# UKU207xx_power_board_1.net
KiCad netlist of a schematic drawn in Altium Designer
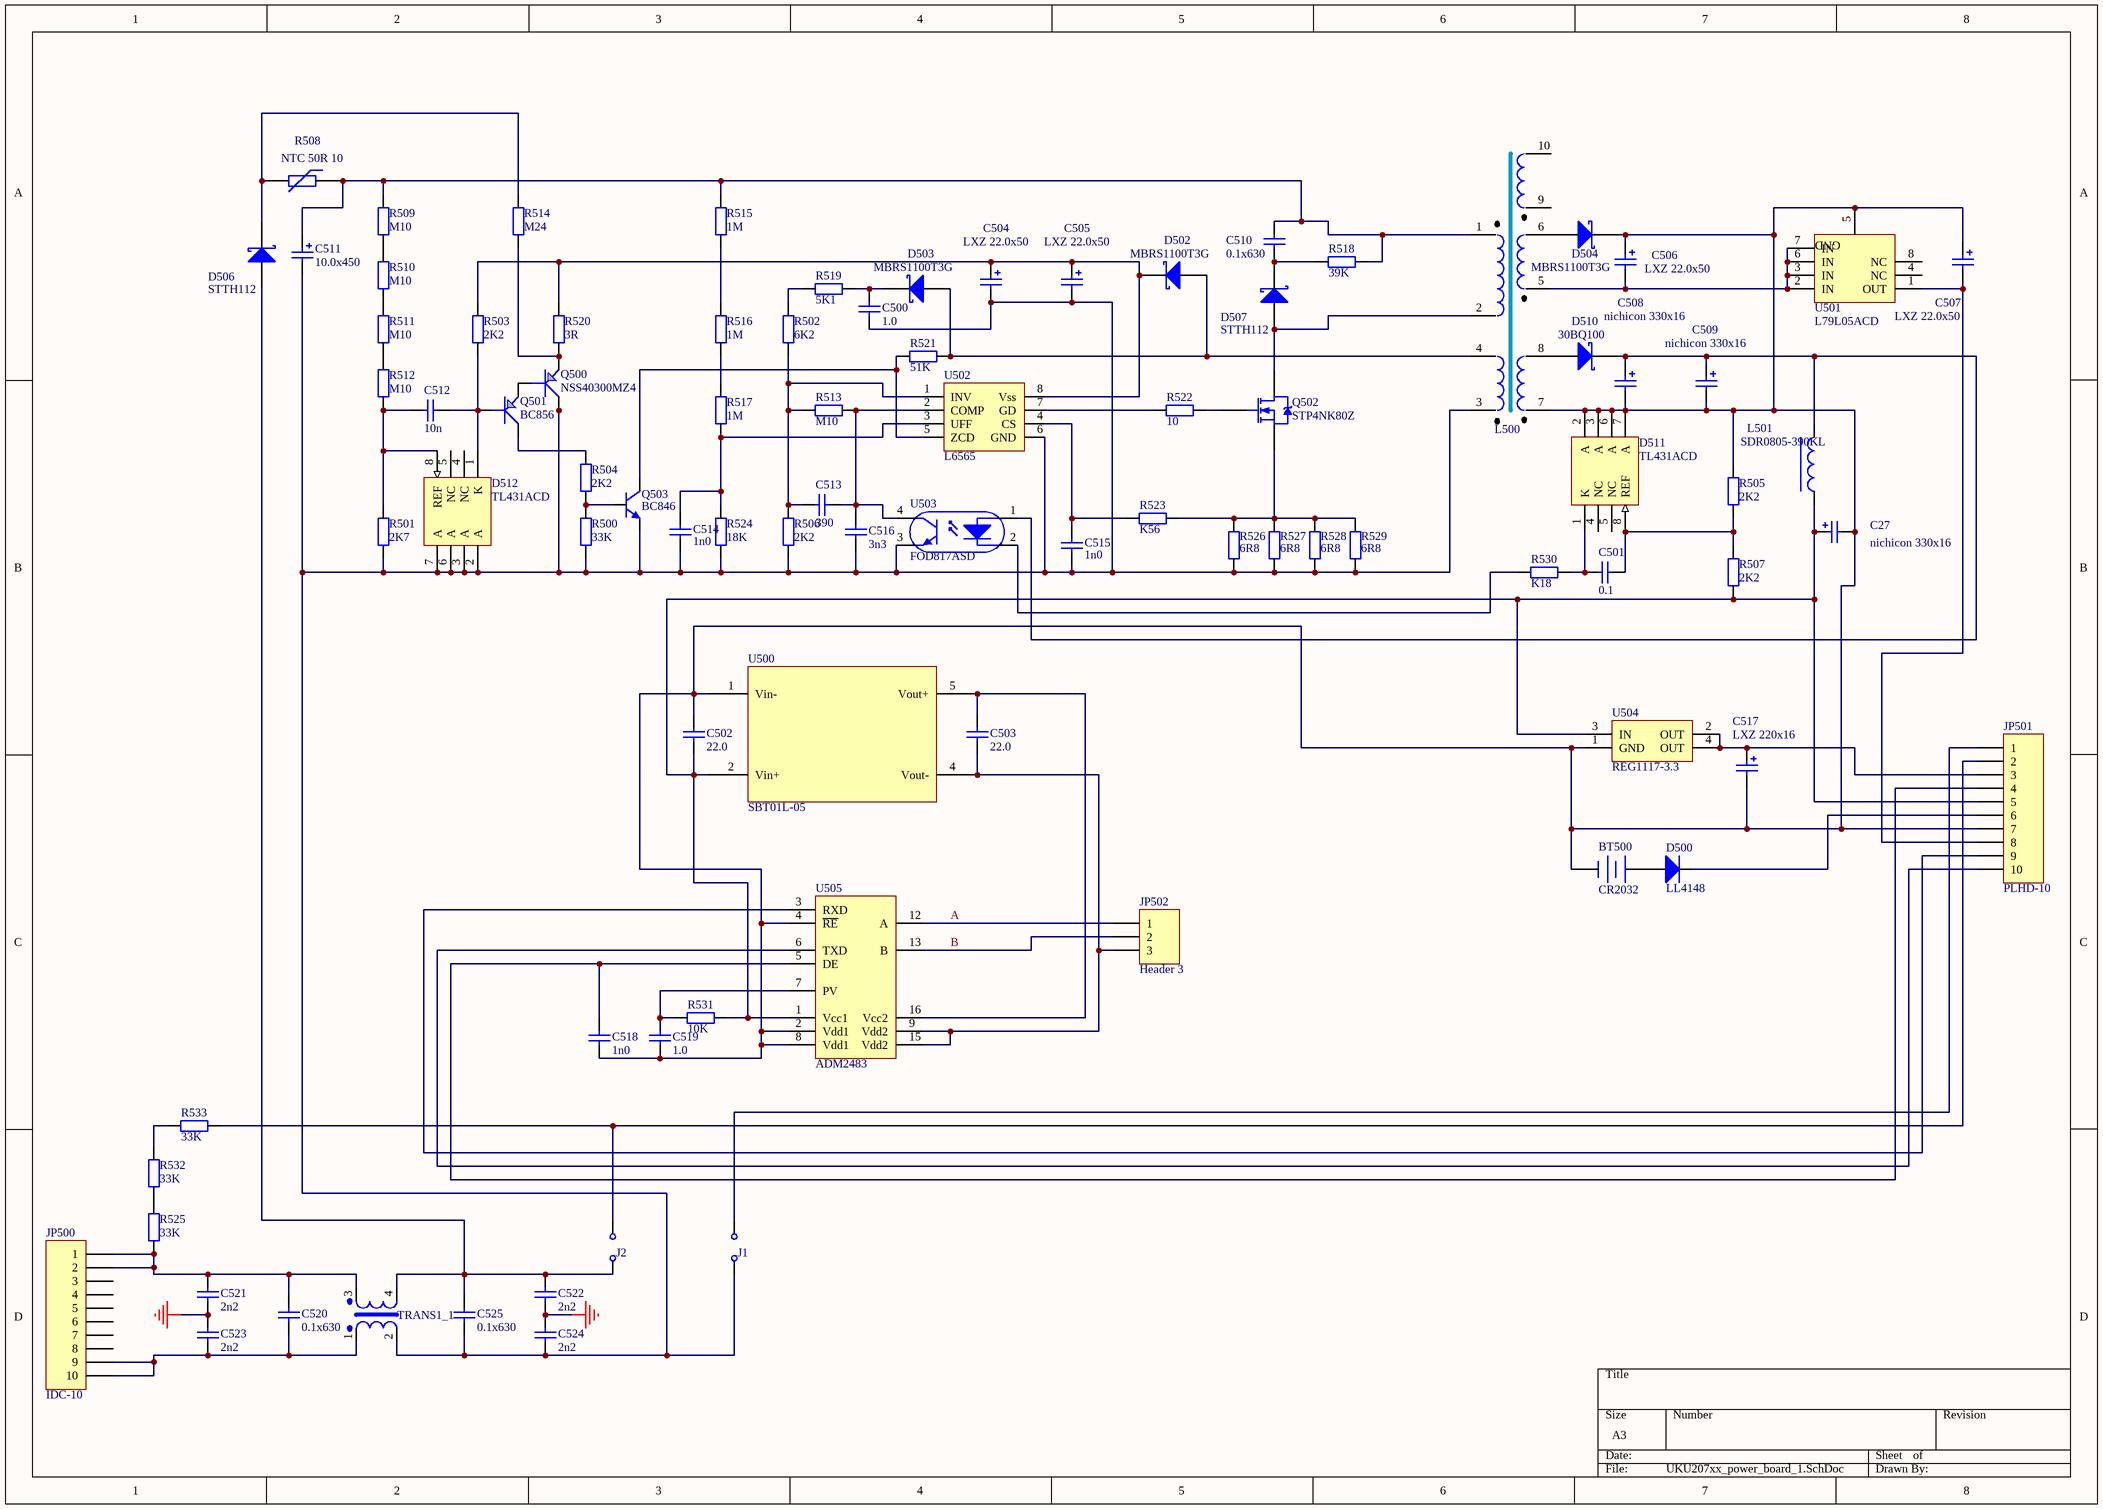
[diagram p0: UKU207xx_power_board_1.SchDoc]

(export (version "E")
  (design (tool "Eeschema 10.0.6"))
  (components
    (comp (ref "BT500")
      (value "CR2032")
      (footprint "BAT_SUPP")
      (description "Multicell Battery")
      (fields (field (name "MANUFACTURER") "Generic Components") (field (name "PUBLISHER") "Altium Limited"))
      (libsource (lib "Miscellaneous Devices") (part "Battery"))
    )
    (comp (ref "C27")
      (value "nichicon 330x16")
      (footprint "el3")
      (description "Polarized Capacitor (Radial)")
      (fields (field (name "MANUFACTURER") "Generic Components") (field (name "PUBLISHER") "Altium Limited"))
      (libsource (lib "PAL") (part "Cap Pol1"))
    )
    (comp (ref "C500")
      (value "1.0")
      (footprint "_1206")
      (description "Capacitor (Semiconductor SIM Model)")
      (fields (field (name "MANUFACTURER") "Generic Components") (field (name "PUBLISHER") "Altium Limited"))
      (libsource (lib "Miscellaneous Devices") (part "Cap Semi"))
    )
    (comp (ref "C501")
      (value "0.1")
      (footprint "_1206")
      (description "Capacitor (Semiconductor SIM Model)")
      (fields (field (name "MANUFACTURER") "Generic Components") (field (name "PUBLISHER") "Altium Limited"))
      (libsource (lib "Miscellaneous Devices") (part "Cap Semi"))
    )
    (comp (ref "C502")
      (value "22.0")
      (footprint "_1206")
      (description "Capacitor (Semiconductor SIM Model)")
      (fields (field (name "MANUFACTURER") "Generic Components") (field (name "PUBLISHER") "Altium Limited"))
      (libsource (lib "Miscellaneous Devices") (part "Cap Semi"))
    )
    (comp (ref "C503")
      (value "22.0")
      (footprint "_1206")
      (description "Capacitor (Semiconductor SIM Model)")
      (fields (field (name "MANUFACTURER") "Generic Components") (field (name "PUBLISHER") "Altium Limited"))
      (libsource (lib "Miscellaneous Devices") (part "Cap Semi"))
    )
    (comp (ref "C504")
      (value "LXZ 22.0x50")
      (footprint "el3")
      (description "Polarized Capacitor (Radial)")
      (fields (field (name "MANUFACTURER") "Generic Components") (field (name "PUBLISHER") "Altium Limited"))
      (libsource (lib "PAL") (part "Cap Pol1"))
    )
    (comp (ref "C505")
      (value "LXZ 22.0x50")
      (footprint "el3")
      (description "Polarized Capacitor (Radial)")
      (fields (field (name "MANUFACTURER") "Generic Components") (field (name "PUBLISHER") "Altium Limited"))
      (libsource (lib "PAL") (part "Cap Pol1"))
    )
    (comp (ref "C506")
      (value "LXZ 22.0x50")
      (footprint "el3")
      (description "Polarized Capacitor (Radial)")
      (fields (field (name "MANUFACTURER") "Generic Components") (field (name "PUBLISHER") "Altium Limited"))
      (libsource (lib "PAL") (part "Cap Pol1"))
    )
    (comp (ref "C507")
      (value "LXZ 22.0x50")
      (footprint "el3")
      (description "Polarized Capacitor (Radial)")
      (fields (field (name "MANUFACTURER") "Generic Components") (field (name "PUBLISHER") "Altium Limited"))
      (libsource (lib "PAL") (part "Cap Pol1"))
    )
    (comp (ref "C508")
      (value "nichicon 330x16")
      (footprint "el3")
      (description "Polarized Capacitor (Radial)")
      (fields (field (name "MANUFACTURER") "Generic Components") (field (name "PUBLISHER") "Altium Limited"))
      (libsource (lib "PAL") (part "Cap Pol1"))
    )
    (comp (ref "C509")
      (value "nichicon 330x16")
      (footprint "el3")
      (description "Polarized Capacitor (Radial)")
      (fields (field (name "MANUFACTURER") "Generic Components") (field (name "PUBLISHER") "Altium Limited"))
      (libsource (lib "PAL") (part "Cap Pol1"))
    )
    (comp (ref "C510")
      (value "0.1x630")
      (footprint "c15")
      (description "Capacitor (Semiconductor SIM Model)")
      (fields (field (name "MANUFACTURER") "Generic Components") (field (name "PUBLISHER") "Altium Limited"))
      (libsource (lib "Miscellaneous Devices") (part "Cap Semi"))
    )
    (comp (ref "C511")
      (value "10.0x450")
      (footprint "el_15_25_h")
      (description "Polarized Capacitor (Radial)")
      (fields (field (name "MANUFACTURER") "Generic Components") (field (name "PUBLISHER") "Altium Limited"))
      (libsource (lib "PAL") (part "Cap Pol1"))
    )
    (comp (ref "C512")
      (value "10n")
      (footprint "_1206")
      (description "Capacitor (Semiconductor SIM Model)")
      (fields (field (name "MANUFACTURER") "Generic Components") (field (name "PUBLISHER") "Altium Limited"))
      (libsource (lib "Miscellaneous Devices") (part "Cap Semi"))
    )
    (comp (ref "C513")
      (value "390")
      (footprint "_1206")
      (description "Capacitor (Semiconductor SIM Model)")
      (fields (field (name "MANUFACTURER") "Generic Components") (field (name "PUBLISHER") "Altium Limited"))
      (libsource (lib "Miscellaneous Devices") (part "Cap Semi"))
    )
    (comp (ref "C514")
      (value "1n0")
      (footprint "_1206")
      (description "Capacitor (Semiconductor SIM Model)")
      (fields (field (name "MANUFACTURER") "Generic Components") (field (name "PUBLISHER") "Altium Limited"))
      (libsource (lib "Miscellaneous Devices") (part "Cap Semi"))
    )
    (comp (ref "C515")
      (value "1n0")
      (footprint "_1206")
      (description "Capacitor (Semiconductor SIM Model)")
      (fields (field (name "MANUFACTURER") "Generic Components") (field (name "PUBLISHER") "Altium Limited"))
      (libsource (lib "Miscellaneous Devices") (part "Cap Semi"))
    )
    (comp (ref "C516")
      (value "3n3")
      (footprint "_1206")
      (description "Capacitor (Semiconductor SIM Model)")
      (fields (field (name "MANUFACTURER") "Generic Components") (field (name "PUBLISHER") "Altium Limited"))
      (libsource (lib "Miscellaneous Devices") (part "Cap Semi"))
    )
    (comp (ref "C517")
      (value "LXZ 220x16")
      (footprint "el3")
      (description "Polarized Capacitor (Radial)")
      (fields (field (name "MANUFACTURER") "Generic Components") (field (name "PUBLISHER") "Altium Limited"))
      (libsource (lib "PAL") (part "Cap Pol1"))
    )
    (comp (ref "C518")
      (value "1n0")
      (footprint "_1206")
      (description "Capacitor (Semiconductor SIM Model)")
      (fields (field (name "MANUFACTURER") "Generic Components") (field (name "PUBLISHER") "Altium Limited"))
      (libsource (lib "Miscellaneous Devices") (part "Cap Semi"))
    )
    (comp (ref "C519")
      (value "1.0")
      (footprint "_1206")
      (description "Capacitor (Semiconductor SIM Model)")
      (fields (field (name "MANUFACTURER") "Generic Components") (field (name "PUBLISHER") "Altium Limited"))
      (libsource (lib "Miscellaneous Devices") (part "Cap Semi"))
    )
    (comp (ref "C520")
      (value "0.1x630")
      (footprint "c15")
      (description "Capacitor (Semiconductor SIM Model)")
      (fields (field (name "MANUFACTURER") "Generic Components") (field (name "PUBLISHER") "Altium Limited"))
      (libsource (lib "Miscellaneous Devices") (part "Cap Semi"))
    )
    (comp (ref "C521")
      (value "2n2")
      (footprint "C8")
      (description "Capacitor (Semiconductor SIM Model)")
      (fields (field (name "MANUFACTURER") "Generic Components") (field (name "PUBLISHER") "Altium Limited"))
      (libsource (lib "Miscellaneous Devices") (part "Cap Semi"))
    )
    (comp (ref "C522")
      (value "2n2")
      (footprint "c8")
      (description "Capacitor (Semiconductor SIM Model)")
      (fields (field (name "MANUFACTURER") "Generic Components") (field (name "PUBLISHER") "Altium Limited"))
      (libsource (lib "Miscellaneous Devices") (part "Cap Semi"))
    )
    (comp (ref "C523")
      (value "2n2")
      (footprint "c8")
      (description "Capacitor (Semiconductor SIM Model)")
      (fields (field (name "MANUFACTURER") "Generic Components") (field (name "PUBLISHER") "Altium Limited"))
      (libsource (lib "Miscellaneous Devices") (part "Cap Semi"))
    )
    (comp (ref "C524")
      (value "2n2")
      (footprint "c8")
      (description "Capacitor (Semiconductor SIM Model)")
      (fields (field (name "MANUFACTURER") "Generic Components") (field (name "PUBLISHER") "Altium Limited"))
      (libsource (lib "Miscellaneous Devices") (part "Cap Semi"))
    )
    (comp (ref "C525")
      (value "0.1х630")
      (footprint "c15")
      (description "Capacitor (Semiconductor SIM Model)")
      (fields (field (name "MANUFACTURER") "Generic Components") (field (name "PUBLISHER") "Altium Limited"))
      (libsource (lib "Miscellaneous Devices") (part "Cap Semi"))
    )
    (comp (ref "D500")
      (value "LL4148")
      (footprint "_1206d")
      (description "Default Diode")
      (fields (field (name "MANUFACTURER") "Generic Components") (field (name "PUBLISHER") "Altium Limited"))
      (libsource (lib "PAL") (part "Diode"))
    )
    (comp (ref "D502")
      (value "MBRS1100T3G")
      (footprint "D_6_3")
      (description "Schottky Rectifier")
      (fields
        (field (name "MANUFACTURER") "International Rectifier")
        (field (name "PUBLISHER") "Altium Limited")
      )
      (libsource (lib "IR Discrete Diode") (part "10BQ015"))
    )
    (comp (ref "D503")
      (value "MBRS1100T3G")
      (footprint "D_6_3")
      (description "Schottky Rectifier")
      (fields
        (field (name "MANUFACTURER") "International Rectifier")
        (field (name "PUBLISHER") "Altium Limited")
      )
      (libsource (lib "IR Discrete Diode") (part "10BQ015"))
    )
    (comp (ref "D504")
      (value "MBRS1100T3G")
      (footprint "D_6_3")
      (description "Schottky Rectifier")
      (fields
        (field (name "MANUFACTURER") "International Rectifier")
        (field (name "PUBLISHER") "Altium Limited")
      )
      (libsource (lib "IR Discrete Diode") (part "10BQ015"))
    )
    (comp (ref "D506")
      (value "STTH112")
      (footprint "D_6_3")
      (description "Schottky Diode")
      (fields
        (field (name "MANUFACTURER") "International Rectifier")
        (field (name "PUBLISHER") "Altium Limited")
      )
      (libsource (lib "IR Discrete Diode") (part "10BQ015"))
    )
    (comp (ref "D507")
      (value "STTH112")
      (footprint "D_6_3")
      (description "Schottky Diode")
      (fields
        (field (name "MANUFACTURER") "International Rectifier")
        (field (name "PUBLISHER") "Altium Limited")
      )
      (libsource (lib "IR Discrete Diode") (part "10BQ015"))
    )
    (comp (ref "D510")
      (value "30BQ100")
      (footprint "30BQ100")
      (description "Schottky Rectifier")
      (fields
        (field (name "MANUFACTURER") "International Rectifier")
        (field (name "PUBLISHER") "Altium Limited")
      )
      (libsource (lib "IR Discrete Diode") (part "10BQ015"))
    )
    (comp (ref "D511")
      (value "TL431ACD")
      (footprint "SO-G8")
      (description "Programmable Precision Reference")
      (fields (field (name "MANUFACTURER") "Motorola") (field (name "PUBLISHER") "Altium Limited"))
      (libsource (lib "") (part "TL431ACD_1"))
    )
    (comp (ref "D512")
      (value "TL431ACD")
      (footprint "SO-G8")
      (description "Programmable Precision Reference")
      (fields (field (name "MANUFACTURER") "Motorola") (field (name "PUBLISHER") "Altium Limited"))
      (libsource (lib "Motorola Power Management Voltage Reference") (part "TL431ACD"))
    )
    (comp (ref "J1")
      (value "~")
      (footprint "BT5-2")
      (description "Switch")
      (fields (field (name "MANUFACTURER") "Generic Components") (field (name "PUBLISHER") "Altium Limited"))
      (libsource (lib "PAL") (part "JMP"))
    )
    (comp (ref "J2")
      (value "~")
      (footprint "BT5-2")
      (description "Switch")
      (fields (field (name "MANUFACTURER") "Generic Components") (field (name "PUBLISHER") "Altium Limited"))
      (libsource (lib "PAL") (part "JMP"))
    )
    (comp (ref "JP500")
      (value "IDC-10")
      (footprint "HDR2X5")
      (description "Header, 10-Pin")
      (fields (field (name "MANUFACTURER") "Generic Components") (field (name "PUBLISHER") "Altium Limited"))
      (libsource (lib "Miscellaneous Connectors") (part "Header 10"))
    )
    (comp (ref "JP501")
      (value "PLHD-10")
      (footprint "HDR2X5")
      (description "Header, 10-Pin")
      (fields (field (name "MANUFACTURER") "Generic Components") (field (name "PUBLISHER") "Altium Limited"))
      (libsource (lib "") (part "Header 10_1"))
    )
    (comp (ref "JP502")
      (value "Header 3")
      (footprint "2EDG-5.08-3P")
      (description "Header, 3-Pin")
      (fields (field (name "MANUFACTURER") "Generic Components") (field (name "PUBLISHER") "Altium Limited"))
      (libsource (lib "Miscellaneous Connectors") (part "Header 3"))
    )
    (comp (ref "L500")
      (value "L220-K10")
      (footprint "trans_ring1")
      (description "Дроссель")
      (libsource (lib "PAL") (part "L1_dc_2"))
    )
    (comp (ref "L501")
      (value "SDR0805-390KL")
      (footprint "L10x10")
      (description "Magnetic-Core Inductor")
      (fields (field (name "MANUFACTURER") "Generic Components") (field (name "PUBLISHER") "Altium Limited"))
      (libsource (lib "PAL") (part "Inductor Konstr 2"))
    )
    (comp (ref "Q500")
      (value "NSS40300MZ4")
      (footprint "DSO-G3")
      (libsource (lib "PAL") (part "NSS40300MZ4"))
    )
    (comp (ref "Q501")
      (value "BC856")
      (footprint "SO-G3")
      (description "Bipolar transistor")
      (libsource (lib "MAIN") (part "GT109"))
    )
    (comp (ref "Q502")
      (value "STP4NK80Z")
      (footprint "TO220_h")
      (description "N-Channel Power MOSFET")
      (fields (field (name "MANUFACTURER") "Generic Components") (field (name "PUBLISHER") "Altium Limited"))
      (libsource (lib "Miscellaneous Devices") (part "NMOS-2"))
    )
    (comp (ref "Q503")
      (value "BC846")
      (footprint "SO-G3")
      (description "General Purpose Transistor NPN Silicon")
      (fields (field (name "MANUFACTURER") "Motorola") (field (name "PUBLISHER") "Altium Limited"))
      (libsource (lib "PAL") (part "BC847ALT1"))
    )
    (comp (ref "R500")
      (value "33K")
      (footprint "_1206")
      (description "Resistor")
      (fields (field (name "MANUFACTURER") "Generic Components") (field (name "PUBLISHER") "Altium Limited"))
      (libsource (lib "") (part "Res2_2"))
    )
    (comp (ref "R501")
      (value "2K7")
      (footprint "_1206")
      (description "Resistor")
      (fields (field (name "MANUFACTURER") "Generic Components") (field (name "PUBLISHER") "Altium Limited"))
      (libsource (lib "") (part "Res2_2"))
    )
    (comp (ref "R502")
      (value "6K2")
      (footprint "_1206")
      (description "Resistor")
      (fields (field (name "MANUFACTURER") "Generic Components") (field (name "PUBLISHER") "Altium Limited"))
      (libsource (lib "") (part "Res2_2"))
    )
    (comp (ref "R503")
      (value "2K2")
      (footprint "_1206")
      (description "Resistor")
      (fields (field (name "MANUFACTURER") "Generic Components") (field (name "PUBLISHER") "Altium Limited"))
      (libsource (lib "") (part "Res2_2"))
    )
    (comp (ref "R504")
      (value "2K2")
      (footprint "_1206")
      (description "Resistor")
      (fields (field (name "MANUFACTURER") "Generic Components") (field (name "PUBLISHER") "Altium Limited"))
      (libsource (lib "") (part "Res2_2"))
    )
    (comp (ref "R505")
      (value "2K2")
      (footprint "_1206")
      (description "Resistor")
      (fields (field (name "MANUFACTURER") "Generic Components") (field (name "PUBLISHER") "Altium Limited"))
      (libsource (lib "") (part "Res2_2"))
    )
    (comp (ref "R506")
      (value "2K2")
      (footprint "_1206")
      (description "Resistor")
      (fields (field (name "MANUFACTURER") "Generic Components") (field (name "PUBLISHER") "Altium Limited"))
      (libsource (lib "") (part "Res2_2"))
    )
    (comp (ref "R507")
      (value "2K2")
      (footprint "_1206")
      (description "Resistor")
      (fields (field (name "MANUFACTURER") "Generic Components") (field (name "PUBLISHER") "Altium Limited"))
      (libsource (lib "") (part "Res2_2"))
    )
    (comp (ref "R508")
      (value "NTC 50R 10")
      (footprint "JVR07N")
      (description "Varistor (Voltage-Sensitive Resistor)")
      (fields (field (name "MANUFACTURER") "Generic Components") (field (name "PUBLISHER") "Altium Limited"))
      (libsource (lib "Miscellaneous Devices") (part "Res Varistor"))
    )
    (comp (ref "R509")
      (value "M10")
      (footprint "_1206")
      (description "Resistor")
      (fields (field (name "MANUFACTURER") "Generic Components") (field (name "PUBLISHER") "Altium Limited"))
      (libsource (lib "") (part "Res2_2"))
    )
    (comp (ref "R510")
      (value "M10")
      (footprint "_1206")
      (description "Resistor")
      (fields (field (name "MANUFACTURER") "Generic Components") (field (name "PUBLISHER") "Altium Limited"))
      (libsource (lib "") (part "Res2_2"))
    )
    (comp (ref "R511")
      (value "M10")
      (footprint "_1206")
      (description "Resistor")
      (fields (field (name "MANUFACTURER") "Generic Components") (field (name "PUBLISHER") "Altium Limited"))
      (libsource (lib "") (part "Res2_2"))
    )
    (comp (ref "R512")
      (value "M10")
      (footprint "_1206")
      (description "Resistor")
      (fields (field (name "MANUFACTURER") "Generic Components") (field (name "PUBLISHER") "Altium Limited"))
      (libsource (lib "") (part "Res2_2"))
    )
    (comp (ref "R513")
      (value "M10")
      (footprint "_1206")
      (description "Resistor")
      (fields (field (name "MANUFACTURER") "Generic Components") (field (name "PUBLISHER") "Altium Limited"))
      (libsource (lib "") (part "Res2_1"))
    )
    (comp (ref "R514")
      (value "M24")
      (footprint "AXIAL-0.7")
      (description "Resistor")
      (fields (field (name "MANUFACTURER") "Generic Components") (field (name "PUBLISHER") "Altium Limited"))
      (libsource (lib "") (part "Res2_2"))
    )
    (comp (ref "R515")
      (value "1M")
      (footprint "_1206")
      (description "Resistor")
      (fields (field (name "MANUFACTURER") "Generic Components") (field (name "PUBLISHER") "Altium Limited"))
      (libsource (lib "") (part "Res2_2"))
    )
    (comp (ref "R516")
      (value "1M")
      (footprint "_1206")
      (description "Resistor")
      (fields (field (name "MANUFACTURER") "Generic Components") (field (name "PUBLISHER") "Altium Limited"))
      (libsource (lib "") (part "Res2_2"))
    )
    (comp (ref "R517")
      (value "1M")
      (footprint "_1206")
      (description "Resistor")
      (fields (field (name "MANUFACTURER") "Generic Components") (field (name "PUBLISHER") "Altium Limited"))
      (libsource (lib "") (part "Res2_2"))
    )
    (comp (ref "R518")
      (value "39K")
      (footprint "AXIAL-0.7")
      (description "Resistor")
      (fields (field (name "MANUFACTURER") "Generic Components") (field (name "PUBLISHER") "Altium Limited"))
      (libsource (lib "") (part "Res2_1"))
    )
    (comp (ref "R519")
      (value "5K1")
      (footprint "_1206")
      (description "Resistor")
      (fields (field (name "MANUFACTURER") "Generic Components") (field (name "PUBLISHER") "Altium Limited"))
      (libsource (lib "") (part "Res2_1"))
    )
    (comp (ref "R520")
      (value "3R")
      (footprint "_1206")
      (description "Resistor")
      (fields (field (name "MANUFACTURER") "Generic Components") (field (name "PUBLISHER") "Altium Limited"))
      (libsource (lib "") (part "Res2_2"))
    )
    (comp (ref "R521")
      (value "51K")
      (footprint "_1206")
      (description "Resistor")
      (fields (field (name "MANUFACTURER") "Generic Components") (field (name "PUBLISHER") "Altium Limited"))
      (libsource (lib "") (part "Res2_1"))
    )
    (comp (ref "R522")
      (value "10")
      (footprint "_1206")
      (description "Resistor")
      (fields (field (name "MANUFACTURER") "Generic Components") (field (name "PUBLISHER") "Altium Limited"))
      (libsource (lib "") (part "Res2_1"))
    )
    (comp (ref "R523")
      (value "K56")
      (footprint "_1206")
      (description "Resistor")
      (fields (field (name "MANUFACTURER") "Generic Components") (field (name "PUBLISHER") "Altium Limited"))
      (libsource (lib "") (part "Res2_1"))
    )
    (comp (ref "R524")
      (value "18K")
      (footprint "_1206")
      (description "Resistor")
      (fields (field (name "MANUFACTURER") "Generic Components") (field (name "PUBLISHER") "Altium Limited"))
      (libsource (lib "") (part "Res2_2"))
    )
    (comp (ref "R525")
      (value "33K")
      (footprint "_1206")
      (description "Resistor")
      (fields (field (name "MANUFACTURER") "Generic Components") (field (name "PUBLISHER") "Altium Limited"))
      (libsource (lib "Miscellaneous Devices") (part "Res2"))
    )
    (comp (ref "R526")
      (value "6R8")
      (footprint "_1206")
      (description "Resistor")
      (fields (field (name "MANUFACTURER") "Generic Components") (field (name "PUBLISHER") "Altium Limited"))
      (libsource (lib "Miscellaneous Devices") (part "Res2"))
    )
    (comp (ref "R527")
      (value "6R8")
      (footprint "_1206")
      (description "Resistor")
      (fields (field (name "MANUFACTURER") "Generic Components") (field (name "PUBLISHER") "Altium Limited"))
      (libsource (lib "Miscellaneous Devices") (part "Res2"))
    )
    (comp (ref "R528")
      (value "6R8")
      (footprint "_1206")
      (description "Resistor")
      (fields (field (name "MANUFACTURER") "Generic Components") (field (name "PUBLISHER") "Altium Limited"))
      (libsource (lib "Miscellaneous Devices") (part "Res2"))
    )
    (comp (ref "R529")
      (value "6R8")
      (footprint "_1206")
      (description "Resistor")
      (fields (field (name "MANUFACTURER") "Generic Components") (field (name "PUBLISHER") "Altium Limited"))
      (libsource (lib "Miscellaneous Devices") (part "Res2"))
    )
    (comp (ref "R530")
      (value "K18")
      (footprint "_1206")
      (description "Resistor")
      (fields (field (name "MANUFACTURER") "Generic Components") (field (name "PUBLISHER") "Altium Limited"))
      (libsource (lib "") (part "Res2_1"))
    )
    (comp (ref "R531")
      (value "10K")
      (footprint "_1206")
      (description "Resistor")
      (fields (field (name "MANUFACTURER") "Generic Components") (field (name "PUBLISHER") "Altium Limited"))
      (libsource (lib "") (part "Res2_1"))
    )
    (comp (ref "R532")
      (value "33K")
      (footprint "_1206")
      (description "Resistor")
      (fields (field (name "MANUFACTURER") "Generic Components") (field (name "PUBLISHER") "Altium Limited"))
      (libsource (lib "Miscellaneous Devices") (part "Res2"))
    )
    (comp (ref "R533")
      (value "33K")
      (footprint "_1206")
      (description "Resistor")
      (fields (field (name "MANUFACTURER") "Generic Components") (field (name "PUBLISHER") "Altium Limited"))
      (libsource (lib "") (part "Res2_1"))
    )
    (comp (ref "T500")
      (value "TRANS1_1")
      (footprint "3030R4")
      (fields (field (name "MANUFACTURER") "Generic Components") (field (name "PUBLISHER") "Altium Limited"))
      (libsource (lib "PAL") (part "TRANS1_1"))
    )
    (comp (ref "U500") (value "SBT01L-05") (footprint "SBT01DET01") (libsource (lib "PAL") (part "SBT01L")))
    (comp (ref "U501")
      (value "L79L05ACD")
      (footprint "SO-G8")
      (description "Negative Voltage Regulator")
      (fields (field (name "MANUFACTURER") "ST-Microelectronics") (field (name "PUBLISHER") "Altium Limited"))
      (libsource (lib "ST Power Mgt Voltage Regulator") (part "L79L05ACD"))
    )
    (comp (ref "U502") (value "L6565") (footprint "so-g8") (libsource (lib "PAL") (part "L6565")))
    (comp (ref "U503") (value "FOD817ASD") (footprint "FOD817ASD") (libsource (lib "PAL") (part "F00817ASD")))
    (comp (ref "U504")
      (value "REG1117-3.3")
      (footprint "DSO-G3")
      (description "800mA and 1A Low Dropout Positive Regulator 2.85V, 3.3V, 5V, and Adjustable")
      (fields (field (name "MANUFACTURER") "Burr-Brown") (field (name "PUBLISHER") "Altium Limited"))
      (libsource (lib "BB Power Mgt Voltage Regulator") (part "REG1117-3.3"))
    )
    (comp (ref "U505") (value "ADM2483") (footprint "SO-G16/D10.4") (libsource (lib "PAL") (part "ADM2483")))
  )
  (nets
    (net (code "1") (name "/A") (class "Default")
      (node (ref "JP502") (pin "1") (pinfunction "1_1") (pintype "passive"))
      (node (ref "U505") (pin "12") (pinfunction "A_12") (pintype "passive"))
    )
    (net (code "2") (name "/B") (class "Default")
      (node (ref "JP502") (pin "2") (pinfunction "2_2") (pintype "passive"))
      (node (ref "U505") (pin "13") (pinfunction "B_13") (pintype "passive"))
    )
    (net (code "3") (name "GND_GND") (class "Default")
      (node (ref "C521") (pin "1") (pinfunction "1_1") (pintype "passive"))
      (node (ref "C522") (pin "1") (pinfunction "1_1") (pintype "passive"))
      (node (ref "C523") (pin "2") (pinfunction "2_2") (pintype "passive"))
      (node (ref "C524") (pin "2") (pinfunction "2_2") (pintype "passive"))
    )
    (net (code "4") (name "Net-(BT500-+)") (class "Default")
      (node (ref "BT500") (pin "1") (pinfunction "+_1") (pintype "passive"))
      (node (ref "D500") (pin "1") (pinfunction "A_1") (pintype "passive"))
    )
    (net (code "5") (name "Net-(BT500--)") (class "Default")
      (node (ref "BT500") (pin "2") (pinfunction "-_2") (pintype "passive"))
      (node (ref "C27") (pin "2") (pinfunction "2_2") (pintype "passive"))
      (node (ref "C502") (pin "1") (pinfunction "1_1") (pintype "passive"))
      (node (ref "C506") (pin "1") (pinfunction "1_1") (pintype "passive"))
      (node (ref "C507") (pin "1") (pinfunction "1_1") (pintype "passive"))
      (node (ref "C508") (pin "2") (pinfunction "2_2") (pintype "passive"))
      (node (ref "C509") (pin "2") (pinfunction "2_2") (pintype "passive"))
      (node (ref "C517") (pin "2") (pinfunction "2_2") (pintype "passive"))
      (node (ref "C518") (pin "1") (pinfunction "1_1") (pintype "passive"))
      (node (ref "C519") (pin "1") (pinfunction "1_1") (pintype "passive"))
      (node (ref "D504") (pin "2") (pinfunction "K_2") (pintype "passive"))
      (node (ref "D511") (pin "2") (pinfunction "A_2") (pintype "passive"))
      (node (ref "D511") (pin "3") (pinfunction "A_3") (pintype "passive"))
      (node (ref "D511") (pin "6") (pinfunction "A_6") (pintype "passive"))
      (node (ref "D511") (pin "7") (pinfunction "A_7") (pintype "passive"))
      (node (ref "JP501") (pin "7") (pinfunction "7_7") (pintype "passive"))
      (node (ref "L500") (pin "7") (pintype "passive"))
      (node (ref "R505") (pin "2") (pinfunction "2_2") (pintype "passive"))
      (node (ref "U500") (pin "1") (pinfunction "Vin-_1") (pintype "passive"))
      (node (ref "U501") (pin "5") (pinfunction "GND_5") (pintype "power_in"))
      (node (ref "U504") (pin "1") (pinfunction "GND_1") (pintype "power_in"))
      (node (ref "U505") (pin "2") (pinfunction "Vdd1_2") (pintype "passive"))
      (node (ref "U505") (pin "4") (pinfunction "~{RE}_4") (pintype "passive"))
      (node (ref "U505") (pin "8") (pinfunction "Vdd1_8") (pintype "passive"))
    )
    (net (code "6") (name "Net-(C506-Pad2)") (class "Default")
      (node (ref "C506") (pin "2") (pinfunction "2_2") (pintype "passive"))
      (node (ref "L500") (pin "5") (pintype "passive"))
      (node (ref "U501") (pin "2") (pinfunction "IN_2") (pintype "power_in"))
      (node (ref "U501") (pin "3") (pinfunction "IN_3") (pintype "power_in"))
      (node (ref "U501") (pin "6") (pinfunction "IN_6") (pintype "power_in"))
      (node (ref "U501") (pin "7") (pinfunction "IN_7") (pintype "power_in"))
    )
    (net (code "7") (name "Net-(C510-Pad2)") (class "Default")
      (node (ref "C510") (pin "2") (pinfunction "2_2") (pintype "passive"))
      (node (ref "C511") (pin "1") (pinfunction "1_1") (pintype "passive"))
      (node (ref "L500") (pin "1") (pintype "passive"))
      (node (ref "R508") (pin "1") (pinfunction "1_1") (pintype "passive"))
      (node (ref "R509") (pin "2") (pinfunction "2_2") (pintype "passive"))
      (node (ref "R515") (pin "2") (pinfunction "2_2") (pintype "passive"))
      (node (ref "R518") (pin "1") (pinfunction "1_1") (pintype "passive"))
    )
    (net (code "8") (name "Net-(C517-Pad1)") (class "Default")
      (node (ref "C517") (pin "1") (pinfunction "1_1") (pintype "passive"))
      (node (ref "JP501") (pin "3") (pinfunction "3_3") (pintype "passive"))
      (node (ref "U504") (pin "2") (pinfunction "OUT_2") (pintype "power_in"))
      (node (ref "U504") (pin "4") (pinfunction "OUT_4") (pintype "power_in"))
    )
    (net (code "9") (name "Net-(D500-K)") (class "Default")
      (node (ref "D500") (pin "2") (pinfunction "K_2") (pintype "passive"))
      (node (ref "JP501") (pin "6") (pinfunction "6_6") (pintype "passive"))
    )
    (net (code "10") (name "Net-(D502-A)") (class "Default")
      (node (ref "D502") (pin "1") (pinfunction "A_1") (pintype "passive"))
      (node (ref "D503") (pin "1") (pinfunction "A_1") (pintype "passive"))
      (node (ref "L500") (pin "4") (pintype "passive"))
      (node (ref "R521") (pin "1") (pinfunction "1_1") (pintype "passive"))
    )
    (net (code "11") (name "Net-(D502-K)") (class "Default")
      (node (ref "C504") (pin "1") (pinfunction "1_1") (pintype "passive"))
      (node (ref "C505") (pin "1") (pinfunction "1_1") (pintype "passive"))
      (node (ref "D502") (pin "2") (pinfunction "K_2") (pintype "passive"))
      (node (ref "R503") (pin "2") (pinfunction "2_2") (pintype "passive"))
      (node (ref "R520") (pin "2") (pinfunction "2_2") (pintype "passive"))
      (node (ref "U502") (pin "8") (pinfunction "Vss_8") (pintype "passive"))
    )
    (net (code "12") (name "Net-(D503-K)") (class "Default")
      (node (ref "C500") (pin "2") (pinfunction "2_2") (pintype "passive"))
      (node (ref "D503") (pin "2") (pinfunction "K_2") (pintype "passive"))
      (node (ref "R519") (pin "1") (pinfunction "1_1") (pintype "passive"))
    )
    (net (code "13") (name "Net-(D504-A)") (class "Default")
      (node (ref "D504") (pin "1") (pinfunction "A_1") (pintype "passive"))
      (node (ref "L500") (pin "6") (pintype "passive"))
    )
    (net (code "14") (name "Net-(D506-A)") (class "Default")
      (node (ref "C522") (pin "2") (pinfunction "2_2") (pintype "passive"))
      (node (ref "C525") (pin "2") (pinfunction "2_2") (pintype "passive"))
      (node (ref "D506") (pin "1") (pinfunction "A_1") (pintype "passive"))
      (node (ref "J2") (pin "1") (pinfunction "1_1") (pintype "passive"))
      (node (ref "T500") (pin "4") (pinfunction "Sec1-_4") (pintype "passive"))
    )
    (net (code "15") (name "Net-(D506-K)") (class "Default")
      (node (ref "D506") (pin "2") (pinfunction "K_2") (pintype "passive"))
      (node (ref "R508") (pin "2") (pinfunction "2_2") (pintype "passive"))
      (node (ref "R514") (pin "2") (pinfunction "2_2") (pintype "passive"))
    )
    (net (code "16") (name "Net-(D507-A)") (class "Default")
      (node (ref "D507") (pin "1") (pinfunction "A_1") (pintype "passive"))
      (node (ref "L500") (pin "2") (pintype "passive"))
      (node (ref "Q502") (pin "2") (pinfunction "D_2") (pintype "passive"))
    )
    (net (code "17") (name "Net-(D507-K)") (class "Default")
      (node (ref "C510") (pin "1") (pinfunction "1_1") (pintype "passive"))
      (node (ref "D507") (pin "2") (pinfunction "K_2") (pintype "passive"))
      (node (ref "R518") (pin "2") (pinfunction "2_2") (pintype "passive"))
    )
    (net (code "18") (name "Net-(D510-A)") (class "Default")
      (node (ref "D510") (pin "1") (pinfunction "A_1") (pintype "passive"))
      (node (ref "L500") (pin "8") (pintype "passive"))
    )
    (net (code "19") (name "Net-(D510-K)") (class "Default")
      (node (ref "C508") (pin "1") (pinfunction "1_1") (pintype "passive"))
      (node (ref "C509") (pin "1") (pinfunction "1_1") (pintype "passive"))
      (node (ref "D510") (pin "2") (pinfunction "K_2") (pintype "passive"))
      (node (ref "L501") (pin "2") (pinfunction "2_2") (pintype "passive"))
      (node (ref "U503") (pin "1") (pinfunction "0_1") (pintype "passive"))
    )
    (net (code "20") (name "Net-(D511-K)") (class "Default")
      (node (ref "C501") (pin "2") (pinfunction "2_2") (pintype "passive"))
      (node (ref "D511") (pin "1") (pinfunction "K_1") (pintype "passive"))
      (node (ref "R530") (pin "1") (pinfunction "1_1") (pintype "passive"))
    )
    (net (code "21") (name "Net-(D511-REF)") (class "Default")
      (node (ref "C501") (pin "1") (pinfunction "1_1") (pintype "passive"))
      (node (ref "D511") (pin "8") (pinfunction "REF_8") (pintype "input"))
      (node (ref "R505") (pin "1") (pinfunction "1_1") (pintype "passive"))
      (node (ref "R507") (pin "2") (pinfunction "2_2") (pintype "passive"))
    )
    (net (code "22") (name "Net-(D512-K)") (class "Default")
      (node (ref "C512") (pin "1") (pinfunction "1_1") (pintype "passive"))
      (node (ref "D512") (pin "1") (pinfunction "K_1") (pintype "passive"))
      (node (ref "Q501") (pin "1") (pinfunction "B_1") (pintype "passive"))
      (node (ref "R503") (pin "1") (pinfunction "1_1") (pintype "passive"))
    )
    (net (code "23") (name "Net-(D512-REF)") (class "Default")
      (node (ref "C512") (pin "2") (pinfunction "2_2") (pintype "passive"))
      (node (ref "D512") (pin "8") (pinfunction "REF_8") (pintype "input"))
      (node (ref "R501") (pin "2") (pinfunction "2_2") (pintype "passive"))
      (node (ref "R512") (pin "1") (pinfunction "1_1") (pintype "passive"))
    )
    (net (code "24") (name "Net-(J1-Pad2)") (class "Default")
      (node (ref "J1") (pin "2") (pinfunction "2_2") (pintype "passive"))
      (node (ref "JP501") (pin "1") (pinfunction "1_1") (pintype "passive"))
    )
    (net (code "25") (name "Net-(J2-Pad2)") (class "Default")
      (node (ref "J2") (pin "2") (pinfunction "2_2") (pintype "passive"))
      (node (ref "JP501") (pin "2") (pinfunction "2_2") (pintype "passive"))
      (node (ref "R533") (pin "1") (pinfunction "1_1") (pintype "passive"))
    )
    (net (code "26") (name "Net-(Q500-B)") (class "Default")
      (node (ref "Q500") (pin "1") (pinfunction "B_1") (pintype "passive"))
      (node (ref "Q501") (pin "2") (pinfunction "E_2") (pintype "passive"))
    )
    (net (code "27") (name "Net-(Q500-E)") (class "Default")
      (node (ref "Q500") (pin "3") (pinfunction "E_3") (pintype "passive"))
      (node (ref "R514") (pin "1") (pinfunction "1_1") (pintype "passive"))
      (node (ref "R520") (pin "1") (pinfunction "1_1") (pintype "passive"))
    )
    (net (code "28") (name "Net-(Q501-C)") (class "Default")
      (node (ref "Q501") (pin "3") (pinfunction "C_3") (pintype "passive"))
      (node (ref "R504") (pin "2") (pinfunction "2_2") (pintype "passive"))
    )
    (net (code "29") (name "Net-(Q502-G)") (class "Default")
      (node (ref "Q502") (pin "1") (pinfunction "G_1") (pintype "passive"))
      (node (ref "R522") (pin "1") (pinfunction "1_1") (pintype "passive"))
    )
    (net (code "30") (name "Net-(Q502-S)") (class "Default")
      (node (ref "Q502") (pin "3") (pinfunction "S_3") (pintype "passive"))
      (node (ref "R523") (pin "1") (pinfunction "1_1") (pintype "passive"))
      (node (ref "R526") (pin "1") (pinfunction "1_1") (pintype "passive"))
      (node (ref "R527") (pin "1") (pinfunction "1_1") (pintype "passive"))
      (node (ref "R528") (pin "1") (pinfunction "1_1") (pintype "passive"))
      (node (ref "R529") (pin "1") (pinfunction "1_1") (pintype "passive"))
    )
    (net (code "31") (name "Net-(Q503-B)") (class "Default")
      (node (ref "Q503") (pin "1") (pinfunction "B_1") (pintype "passive"))
      (node (ref "R500") (pin "2") (pinfunction "2_2") (pintype "passive"))
      (node (ref "R504") (pin "1") (pinfunction "1_1") (pintype "passive"))
    )
    (net (code "32") (name "Net-(Q503-C)") (class "Default")
      (node (ref "Q503") (pin "3") (pinfunction "C_3") (pintype "passive"))
      (node (ref "R521") (pin "2") (pinfunction "2_2") (pintype "passive"))
      (node (ref "U502") (pin "5") (pinfunction "ZCD_5") (pintype "passive"))
    )
    (net (code "33") (name "Net-(Q503-E)") (class "Default")
      (node (ref "C500") (pin "1") (pinfunction "1_1") (pintype "passive"))
      (node (ref "C504") (pin "2") (pinfunction "2_2") (pintype "passive"))
      (node (ref "C505") (pin "2") (pinfunction "2_2") (pintype "passive"))
      (node (ref "C511") (pin "2") (pinfunction "2_2") (pintype "passive"))
      (node (ref "C514") (pin "2") (pinfunction "2_2") (pintype "passive"))
      (node (ref "C515") (pin "2") (pinfunction "2_2") (pintype "passive"))
      (node (ref "C516") (pin "1") (pinfunction "1_1") (pintype "passive"))
      (node (ref "C524") (pin "1") (pinfunction "1_1") (pintype "passive"))
      (node (ref "C525") (pin "1") (pinfunction "1_1") (pintype "passive"))
      (node (ref "D512") (pin "2") (pinfunction "A_2") (pintype "passive"))
      (node (ref "D512") (pin "3") (pinfunction "A_3") (pintype "passive"))
      (node (ref "D512") (pin "6") (pinfunction "A_6") (pintype "passive"))
      (node (ref "D512") (pin "7") (pinfunction "A_7") (pintype "passive"))
      (node (ref "J1") (pin "1") (pinfunction "1_1") (pintype "passive"))
      (node (ref "L500") (pin "3") (pintype "passive"))
      (node (ref "Q500") (pin "2") (pinfunction "C_2") (pintype "passive"))
      (node (ref "Q500") (pin "4") (pinfunction "C_4") (pintype "passive"))
      (node (ref "Q503") (pin "2") (pinfunction "E_2") (pintype "passive"))
      (node (ref "R500") (pin "1") (pinfunction "1_1") (pintype "passive"))
      (node (ref "R501") (pin "1") (pinfunction "1_1") (pintype "passive"))
      (node (ref "R506") (pin "1") (pinfunction "1_1") (pintype "passive"))
      (node (ref "R524") (pin "1") (pinfunction "1_1") (pintype "passive"))
      (node (ref "R526") (pin "2") (pinfunction "2_2") (pintype "passive"))
      (node (ref "R527") (pin "2") (pinfunction "2_2") (pintype "passive"))
      (node (ref "R528") (pin "2") (pinfunction "2_2") (pintype "passive"))
      (node (ref "R529") (pin "2") (pinfunction "2_2") (pintype "passive"))
      (node (ref "T500") (pin "2") (pinfunction "Pri-_2") (pintype "passive"))
      (node (ref "U502") (pin "6") (pinfunction "GND_6") (pintype "passive"))
      (node (ref "U503") (pin "3") (pinfunction "4_3") (pintype "passive"))
    )
    (net (code "34") (name "Net-(R502-Pad2)") (class "Default")
      (node (ref "R502") (pin "2") (pinfunction "2_2") (pintype "passive"))
      (node (ref "R519") (pin "2") (pinfunction "2_2") (pintype "passive"))
    )
    (net (code "35") (name "Net-(R509-Pad1)") (class "Default")
      (node (ref "R509") (pin "1") (pinfunction "1_1") (pintype "passive"))
      (node (ref "R510") (pin "2") (pinfunction "2_2") (pintype "passive"))
    )
    (net (code "36") (name "Net-(R510-Pad1)") (class "Default")
      (node (ref "R510") (pin "1") (pinfunction "1_1") (pintype "passive"))
      (node (ref "R511") (pin "2") (pinfunction "2_2") (pintype "passive"))
    )
    (net (code "37") (name "Net-(R511-Pad1)") (class "Default")
      (node (ref "R511") (pin "1") (pinfunction "1_1") (pintype "passive"))
      (node (ref "R512") (pin "2") (pinfunction "2_2") (pintype "passive"))
    )
    (net (code "38") (name "Net-(R515-Pad1)") (class "Default")
      (node (ref "R515") (pin "1") (pinfunction "1_1") (pintype "passive"))
      (node (ref "R516") (pin "2") (pinfunction "2_2") (pintype "passive"))
    )
    (net (code "39") (name "Net-(R516-Pad1)") (class "Default")
      (node (ref "R516") (pin "1") (pinfunction "1_1") (pintype "passive"))
      (node (ref "R517") (pin "2") (pinfunction "2_2") (pintype "passive"))
    )
    (net (code "40") (name "Net-(R525-Pad1)") (class "Default")
      (node (ref "R525") (pin "1") (pinfunction "1_1") (pintype "passive"))
      (node (ref "R532") (pin "2") (pinfunction "2_2") (pintype "passive"))
    )
    (net (code "41") (name "Net-(R532-Pad1)") (class "Default")
      (node (ref "R532") (pin "1") (pinfunction "1_1") (pintype "passive"))
      (node (ref "R533") (pin "2") (pinfunction "2_2") (pintype "passive"))
    )
    (net (code "42") (name "Net-(T500-Pri+)") (class "Default")
      (node (ref "C520") (pin "1") (pinfunction "1_1") (pintype "passive"))
      (node (ref "C523") (pin "1") (pinfunction "1_1") (pintype "passive"))
      (node (ref "JP500") (pin "10") (pinfunction "10_10") (pintype "passive"))
      (node (ref "JP500") (pin "9") (pinfunction "9_9") (pintype "passive"))
      (node (ref "T500") (pin "1") (pinfunction "Pri+_1") (pintype "passive"))
    )
    (net (code "43") (name "Net-(T500-Sec1+)") (class "Default")
      (node (ref "C520") (pin "2") (pinfunction "2_2") (pintype "passive"))
      (node (ref "C521") (pin "2") (pinfunction "2_2") (pintype "passive"))
      (node (ref "JP500") (pin "1") (pinfunction "1_1") (pintype "passive"))
      (node (ref "JP500") (pin "2") (pinfunction "2_2") (pintype "passive"))
      (node (ref "R525") (pin "2") (pinfunction "2_2") (pintype "passive"))
      (node (ref "T500") (pin "3") (pinfunction "Sec1+_3") (pintype "passive"))
    )
    (net (code "44") (name "Net-(U500-Vin+)") (class "Default")
      (node (ref "C27") (pin "1") (pinfunction "1_1") (pintype "passive"))
      (node (ref "C502") (pin "2") (pinfunction "2_2") (pintype "passive"))
      (node (ref "JP501") (pin "5") (pinfunction "5_5") (pintype "passive"))
      (node (ref "L501") (pin "1") (pinfunction "1_1") (pintype "passive"))
      (node (ref "R507") (pin "1") (pinfunction "1_1") (pintype "passive"))
      (node (ref "R531") (pin "1") (pinfunction "1_1") (pintype "passive"))
      (node (ref "U500") (pin "2") (pinfunction "Vin+_2") (pintype "passive"))
      (node (ref "U504") (pin "3") (pinfunction "IN_3") (pintype "power_in"))
      (node (ref "U505") (pin "1") (pinfunction "Vcc1_1") (pintype "passive"))
    )
    (net (code "45") (name "Net-(U500-Vout+)") (class "Default")
      (node (ref "C503") (pin "1") (pinfunction "1_1") (pintype "passive"))
      (node (ref "U500") (pin "5") (pinfunction "Vout+_5") (pintype "passive"))
      (node (ref "U505") (pin "16") (pinfunction "Vcc2_16") (pintype "passive"))
    )
    (net (code "46") (name "Net-(U500-Vout-)") (class "Default")
      (node (ref "C503") (pin "2") (pinfunction "2_2") (pintype "passive"))
      (node (ref "JP502") (pin "3") (pinfunction "3_3") (pintype "passive"))
      (node (ref "U500") (pin "4") (pinfunction "Vout-_4") (pintype "passive"))
      (node (ref "U505") (pin "15") (pinfunction "Vdd2_15") (pintype "passive"))
      (node (ref "U505") (pin "9") (pinfunction "Vdd2_9") (pintype "passive"))
    )
    (net (code "47") (name "Net-(U501-OUT)") (class "Default")
      (node (ref "C507") (pin "2") (pinfunction "2_2") (pintype "passive"))
      (node (ref "JP501") (pin "8") (pinfunction "8_8") (pintype "passive"))
      (node (ref "U501") (pin "1") (pinfunction "OUT_1") (pintype "power_in"))
    )
    (net (code "48") (name "Net-(U502-COMP)") (class "Default")
      (node (ref "C513") (pin "2") (pinfunction "2_2") (pintype "passive"))
      (node (ref "C516") (pin "2") (pinfunction "2_2") (pintype "passive"))
      (node (ref "R513") (pin "1") (pinfunction "1_1") (pintype "passive"))
      (node (ref "U502") (pin "2") (pinfunction "COMP_2") (pintype "passive"))
      (node (ref "U503") (pin "4") (pinfunction "2_4") (pintype "passive"))
    )
    (net (code "49") (name "Net-(U502-CS)") (class "Default")
      (node (ref "C515") (pin "1") (pinfunction "1_1") (pintype "passive"))
      (node (ref "R523") (pin "2") (pinfunction "2_2") (pintype "passive"))
      (node (ref "U502") (pin "4") (pinfunction "CS_4") (pintype "passive"))
    )
    (net (code "50") (name "Net-(U502-GD)") (class "Default")
      (node (ref "R522") (pin "2") (pinfunction "2_2") (pintype "passive"))
      (node (ref "U502") (pin "7") (pinfunction "GD_7") (pintype "passive"))
    )
    (net (code "51") (name "Net-(U502-INV)") (class "Default")
      (node (ref "C513") (pin "1") (pinfunction "1_1") (pintype "passive"))
      (node (ref "R502") (pin "1") (pinfunction "1_1") (pintype "passive"))
      (node (ref "R506") (pin "2") (pinfunction "2_2") (pintype "passive"))
      (node (ref "R513") (pin "2") (pinfunction "2_2") (pintype "passive"))
      (node (ref "U502") (pin "1") (pinfunction "INV_1") (pintype "passive"))
    )
    (net (code "52") (name "Net-(U502-UFF)") (class "Default")
      (node (ref "C514") (pin "1") (pinfunction "1_1") (pintype "passive"))
      (node (ref "R517") (pin "1") (pinfunction "1_1") (pintype "passive"))
      (node (ref "R524") (pin "2") (pinfunction "2_2") (pintype "passive"))
      (node (ref "U502") (pin "3") (pinfunction "UFF_3") (pintype "passive"))
    )
    (net (code "53") (name "Net-(U503-1)") (class "Default")
      (node (ref "R530") (pin "2") (pinfunction "2_2") (pintype "passive"))
      (node (ref "U503") (pin "2") (pinfunction "1_2") (pintype "passive"))
    )
    (net (code "54") (name "Net-(U505-DE)") (class "Default")
      (node (ref "C518") (pin "2") (pinfunction "2_2") (pintype "passive"))
      (node (ref "JP501") (pin "4") (pinfunction "4_4") (pintype "passive"))
      (node (ref "U505") (pin "5") (pinfunction "DE_5") (pintype "passive"))
    )
    (net (code "55") (name "Net-(U505-PV)") (class "Default")
      (node (ref "C519") (pin "2") (pinfunction "2_2") (pintype "passive"))
      (node (ref "R531") (pin "2") (pinfunction "2_2") (pintype "passive"))
      (node (ref "U505") (pin "7") (pinfunction "PV_7") (pintype "passive"))
    )
    (net (code "56") (name "Net-(U505-RXD)") (class "Default")
      (node (ref "JP501") (pin "9") (pinfunction "9_9") (pintype "passive"))
      (node (ref "U505") (pin "3") (pinfunction "RXD_3") (pintype "passive"))
    )
    (net (code "57") (name "Net-(U505-TXD)") (class "Default")
      (node (ref "JP501") (pin "10") (pinfunction "10_10") (pintype "passive"))
      (node (ref "U505") (pin "6") (pinfunction "TXD_6") (pintype "passive"))
    )
    (net (code "58") (name "unconnected-(D511-NC-Pad4)") (class "Default")
      (node (ref "D511") (pin "4") (pinfunction "NC_4") (pintype "passive"))
    )
    (net (code "59") (name "unconnected-(D511-NC-Pad5)") (class "Default")
      (node (ref "D511") (pin "5") (pinfunction "NC_5") (pintype "passive"))
    )
    (net (code "60") (name "unconnected-(D512-NC-Pad4)") (class "Default")
      (node (ref "D512") (pin "4") (pinfunction "NC_4") (pintype "passive"))
    )
    (net (code "61") (name "unconnected-(D512-NC-Pad5)") (class "Default")
      (node (ref "D512") (pin "5") (pinfunction "NC_5") (pintype "passive"))
    )
    (net (code "62") (name "unconnected-(JP500-Pad3)") (class "Default")
      (node (ref "JP500") (pin "3") (pinfunction "3_3") (pintype "passive"))
    )
    (net (code "63") (name "unconnected-(JP500-Pad4)") (class "Default")
      (node (ref "JP500") (pin "4") (pinfunction "4_4") (pintype "passive"))
    )
    (net (code "64") (name "unconnected-(JP500-Pad5)") (class "Default")
      (node (ref "JP500") (pin "5") (pinfunction "5_5") (pintype "passive"))
    )
    (net (code "65") (name "unconnected-(JP500-Pad6)") (class "Default")
      (node (ref "JP500") (pin "6") (pinfunction "6_6") (pintype "passive"))
    )
    (net (code "66") (name "unconnected-(JP500-Pad7)") (class "Default")
      (node (ref "JP500") (pin "7") (pinfunction "7_7") (pintype "passive"))
    )
    (net (code "67") (name "unconnected-(JP500-Pad8)") (class "Default")
      (node (ref "JP500") (pin "8") (pinfunction "8_8") (pintype "passive"))
    )
    (net (code "68") (name "unconnected-(L500-Pad9)") (class "Default")
      (node (ref "L500") (pin "9") (pintype "passive"))
    )
    (net (code "69") (name "unconnected-(L500-Pad10)") (class "Default")
      (node (ref "L500") (pin "10") (pinfunction "10_10") (pintype "passive"))
    )
    (net (code "70") (name "unconnected-(U501-NC-Pad4)") (class "Default")
      (node (ref "U501") (pin "4") (pinfunction "NC_4") (pintype "passive"))
    )
    (net (code "71") (name "unconnected-(U501-NC-Pad8)") (class "Default")
      (node (ref "U501") (pin "8") (pinfunction "NC_8") (pintype "passive"))
    )
  )
)
